# 03_MCU.net
KiCad netlist of a schematic drawn in Altium Designer
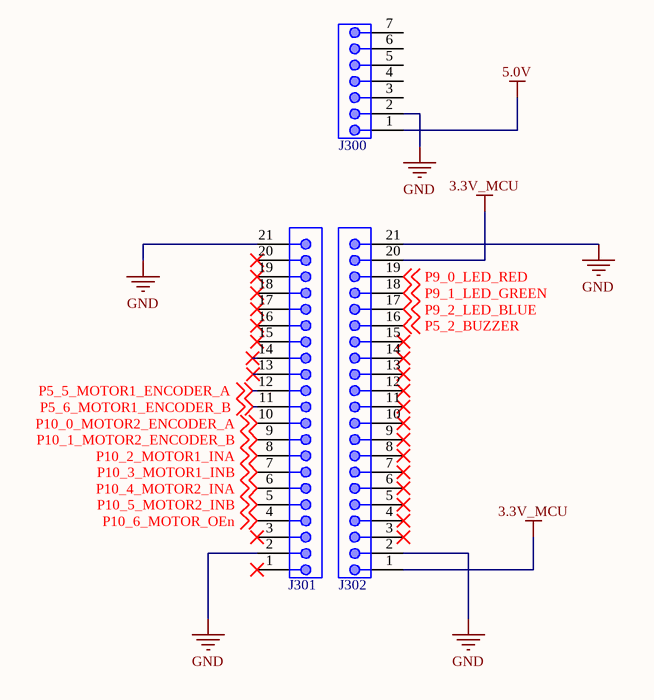
[diagram p0: 03_MCU.SchDoc]

(export (version "E")
  (design (tool "Eeschema 10.0.6"))
  (components
    (comp (ref "J300")
      (value "CONN_HEADER_MALE_1x7")
      (footprint "HDR1X7_Stagger")
      (description "Header, 7-Pin")
      (libsource (lib "ECE453-S22") (part "CONN_HEADER_MALE_1x7"))
    )
    (comp (ref "J301")
      (value "CONN_HEADER_MALE_1x21")
      (footprint "HDR1X21 _Stagger")
      (description "Header, 21-Pin")
      (libsource (lib "Connectors") (part "CONN_HEADER_MALE_1x21"))
    )
    (comp (ref "J302")
      (value "CONN_HEADER_MALE_1x21")
      (footprint "HDR1X21 _Stagger")
      (description "Header, 21-Pin")
      (libsource (lib "Connectors") (part "CONN_HEADER_MALE_1x21"))
    )
  )
  (nets
    (net (code "1") (name "3.3V_MCU") (class "Default")
      (node (ref "J302") (pin "1") (pinfunction "1_1") (pintype "passive"))
      (node (ref "J302") (pin "20") (pinfunction "20_20") (pintype "passive"))
    )
    (net (code "2") (name "5.0V") (class "Default")
      (node (ref "J300") (pin "1") (pinfunction "1_1") (pintype "passive"))
    )
    (net (code "3") (name "GND") (class "Default")
      (node (ref "J300") (pin "2") (pinfunction "2_2") (pintype "passive"))
      (node (ref "J301") (pin "2") (pinfunction "2_2") (pintype "passive"))
      (node (ref "J301") (pin "21") (pinfunction "21_21") (pintype "passive"))
      (node (ref "J302") (pin "2") (pinfunction "2_2") (pintype "passive"))
      (node (ref "J302") (pin "21") (pinfunction "21_21") (pintype "passive"))
    )
    (net (code "4") (name "P5_2_BUZZER") (class "Default")
      (node (ref "J302") (pin "16") (pinfunction "16_16") (pintype "passive"))
    )
    (net (code "5") (name "P5_5_MOTOR1_ENCODER_A") (class "Default")
      (node (ref "J301") (pin "12") (pinfunction "12_12") (pintype "passive"))
    )
    (net (code "6") (name "P5_6_MOTOR1_ENCODER_B") (class "Default")
      (node (ref "J301") (pin "11") (pinfunction "11_11") (pintype "passive"))
    )
    (net (code "7") (name "P9_0_LED_RED") (class "Default")
      (node (ref "J302") (pin "19") (pinfunction "19_19") (pintype "passive"))
    )
    (net (code "8") (name "P9_1_LED_GREEN") (class "Default")
      (node (ref "J302") (pin "18") (pinfunction "18_18") (pintype "passive"))
    )
    (net (code "9") (name "P9_2_LED_BLUE") (class "Default")
      (node (ref "J302") (pin "17") (pinfunction "17_17") (pintype "passive"))
    )
    (net (code "10") (name "P10_0_MOTOR2_ENCODER_A") (class "Default")
      (node (ref "J301") (pin "10") (pinfunction "10_10") (pintype "passive"))
    )
    (net (code "11") (name "P10_1_MOTOR2_ENCODER_B") (class "Default")
      (node (ref "J301") (pin "9") (pinfunction "9_9") (pintype "passive"))
    )
    (net (code "12") (name "P10_2_MOTOR1_INA") (class "Default")
      (node (ref "J301") (pin "8") (pinfunction "8_8") (pintype "passive"))
    )
    (net (code "13") (name "P10_3_MOTOR1_INB") (class "Default")
      (node (ref "J301") (pin "7") (pinfunction "7_7") (pintype "passive"))
    )
    (net (code "14") (name "P10_4_MOTOR2_INA") (class "Default")
      (node (ref "J301") (pin "6") (pinfunction "6_6") (pintype "passive"))
    )
    (net (code "15") (name "P10_5_MOTOR2_INB") (class "Default")
      (node (ref "J301") (pin "5") (pinfunction "5_5") (pintype "passive"))
    )
    (net (code "16") (name "P10_6_MOTOR_OEn") (class "Default")
      (node (ref "J301") (pin "4") (pinfunction "4_4") (pintype "passive"))
    )
    (net (code "17") (name "unconnected-(J300-Pad3)") (class "Default")
      (node (ref "J300") (pin "3") (pinfunction "3_3") (pintype "passive"))
    )
    (net (code "18") (name "unconnected-(J300-Pad4)") (class "Default")
      (node (ref "J300") (pin "4") (pinfunction "4_4") (pintype "passive"))
    )
    (net (code "19") (name "unconnected-(J300-Pad5)") (class "Default")
      (node (ref "J300") (pin "5") (pinfunction "5_5") (pintype "passive"))
    )
    (net (code "20") (name "unconnected-(J300-Pad6)") (class "Default")
      (node (ref "J300") (pin "6") (pinfunction "6_6") (pintype "passive"))
    )
    (net (code "21") (name "unconnected-(J300-Pad7)") (class "Default")
      (node (ref "J300") (pin "7") (pinfunction "7_7") (pintype "passive"))
    )
    (net (code "22") (name "unconnected-(J301-Pad1)") (class "Default")
      (node (ref "J301") (pin "1") (pinfunction "1_1") (pintype "passive+no_connect"))
    )
    (net (code "23") (name "unconnected-(J301-Pad3)") (class "Default")
      (node (ref "J301") (pin "3") (pinfunction "3_3") (pintype "passive+no_connect"))
    )
    (net (code "24") (name "unconnected-(J301-Pad13)") (class "Default")
      (node (ref "J301") (pin "13") (pinfunction "13_13") (pintype "passive+no_connect"))
    )
    (net (code "25") (name "unconnected-(J301-Pad14)") (class "Default")
      (node (ref "J301") (pin "14") (pinfunction "14_14") (pintype "passive+no_connect"))
    )
    (net (code "26") (name "unconnected-(J301-Pad15)") (class "Default")
      (node (ref "J301") (pin "15") (pinfunction "15_15") (pintype "passive+no_connect"))
    )
    (net (code "27") (name "unconnected-(J301-Pad16)") (class "Default")
      (node (ref "J301") (pin "16") (pinfunction "16_16") (pintype "passive+no_connect"))
    )
    (net (code "28") (name "unconnected-(J301-Pad17)") (class "Default")
      (node (ref "J301") (pin "17") (pinfunction "17_17") (pintype "passive+no_connect"))
    )
    (net (code "29") (name "unconnected-(J301-Pad18)") (class "Default")
      (node (ref "J301") (pin "18") (pinfunction "18_18") (pintype "passive+no_connect"))
    )
    (net (code "30") (name "unconnected-(J301-Pad19)") (class "Default")
      (node (ref "J301") (pin "19") (pinfunction "19_19") (pintype "passive+no_connect"))
    )
    (net (code "31") (name "unconnected-(J301-Pad20)") (class "Default")
      (node (ref "J301") (pin "20") (pinfunction "20_20") (pintype "passive+no_connect"))
    )
    (net (code "32") (name "unconnected-(J302-Pad3)") (class "Default")
      (node (ref "J302") (pin "3") (pinfunction "3_3") (pintype "passive+no_connect"))
    )
    (net (code "33") (name "unconnected-(J302-Pad4)") (class "Default")
      (node (ref "J302") (pin "4") (pinfunction "4_4") (pintype "passive+no_connect"))
    )
    (net (code "34") (name "unconnected-(J302-Pad5)") (class "Default")
      (node (ref "J302") (pin "5") (pinfunction "5_5") (pintype "passive+no_connect"))
    )
    (net (code "35") (name "unconnected-(J302-Pad6)") (class "Default")
      (node (ref "J302") (pin "6") (pinfunction "6_6") (pintype "passive+no_connect"))
    )
    (net (code "36") (name "unconnected-(J302-Pad7)") (class "Default")
      (node (ref "J302") (pin "7") (pinfunction "7_7") (pintype "passive+no_connect"))
    )
    (net (code "37") (name "unconnected-(J302-Pad8)") (class "Default")
      (node (ref "J302") (pin "8") (pinfunction "8_8") (pintype "passive+no_connect"))
    )
    (net (code "38") (name "unconnected-(J302-Pad9)") (class "Default")
      (node (ref "J302") (pin "9") (pinfunction "9_9") (pintype "passive+no_connect"))
    )
    (net (code "39") (name "unconnected-(J302-Pad10)") (class "Default")
      (node (ref "J302") (pin "10") (pinfunction "10_10") (pintype "passive+no_connect"))
    )
    (net (code "40") (name "unconnected-(J302-Pad11)") (class "Default")
      (node (ref "J302") (pin "11") (pinfunction "11_11") (pintype "passive+no_connect"))
    )
    (net (code "41") (name "unconnected-(J302-Pad12)") (class "Default")
      (node (ref "J302") (pin "12") (pinfunction "12_12") (pintype "passive+no_connect"))
    )
    (net (code "42") (name "unconnected-(J302-Pad13)") (class "Default")
      (node (ref "J302") (pin "13") (pinfunction "13_13") (pintype "passive+no_connect"))
    )
    (net (code "43") (name "unconnected-(J302-Pad14)") (class "Default")
      (node (ref "J302") (pin "14") (pinfunction "14_14") (pintype "passive+no_connect"))
    )
    (net (code "44") (name "unconnected-(J302-Pad15)") (class "Default")
      (node (ref "J302") (pin "15") (pinfunction "15_15") (pintype "passive+no_connect"))
    )
  )
)
